# Flex-touch.net
KiCad netlist of a schematic drawn in EasyEDA Pro
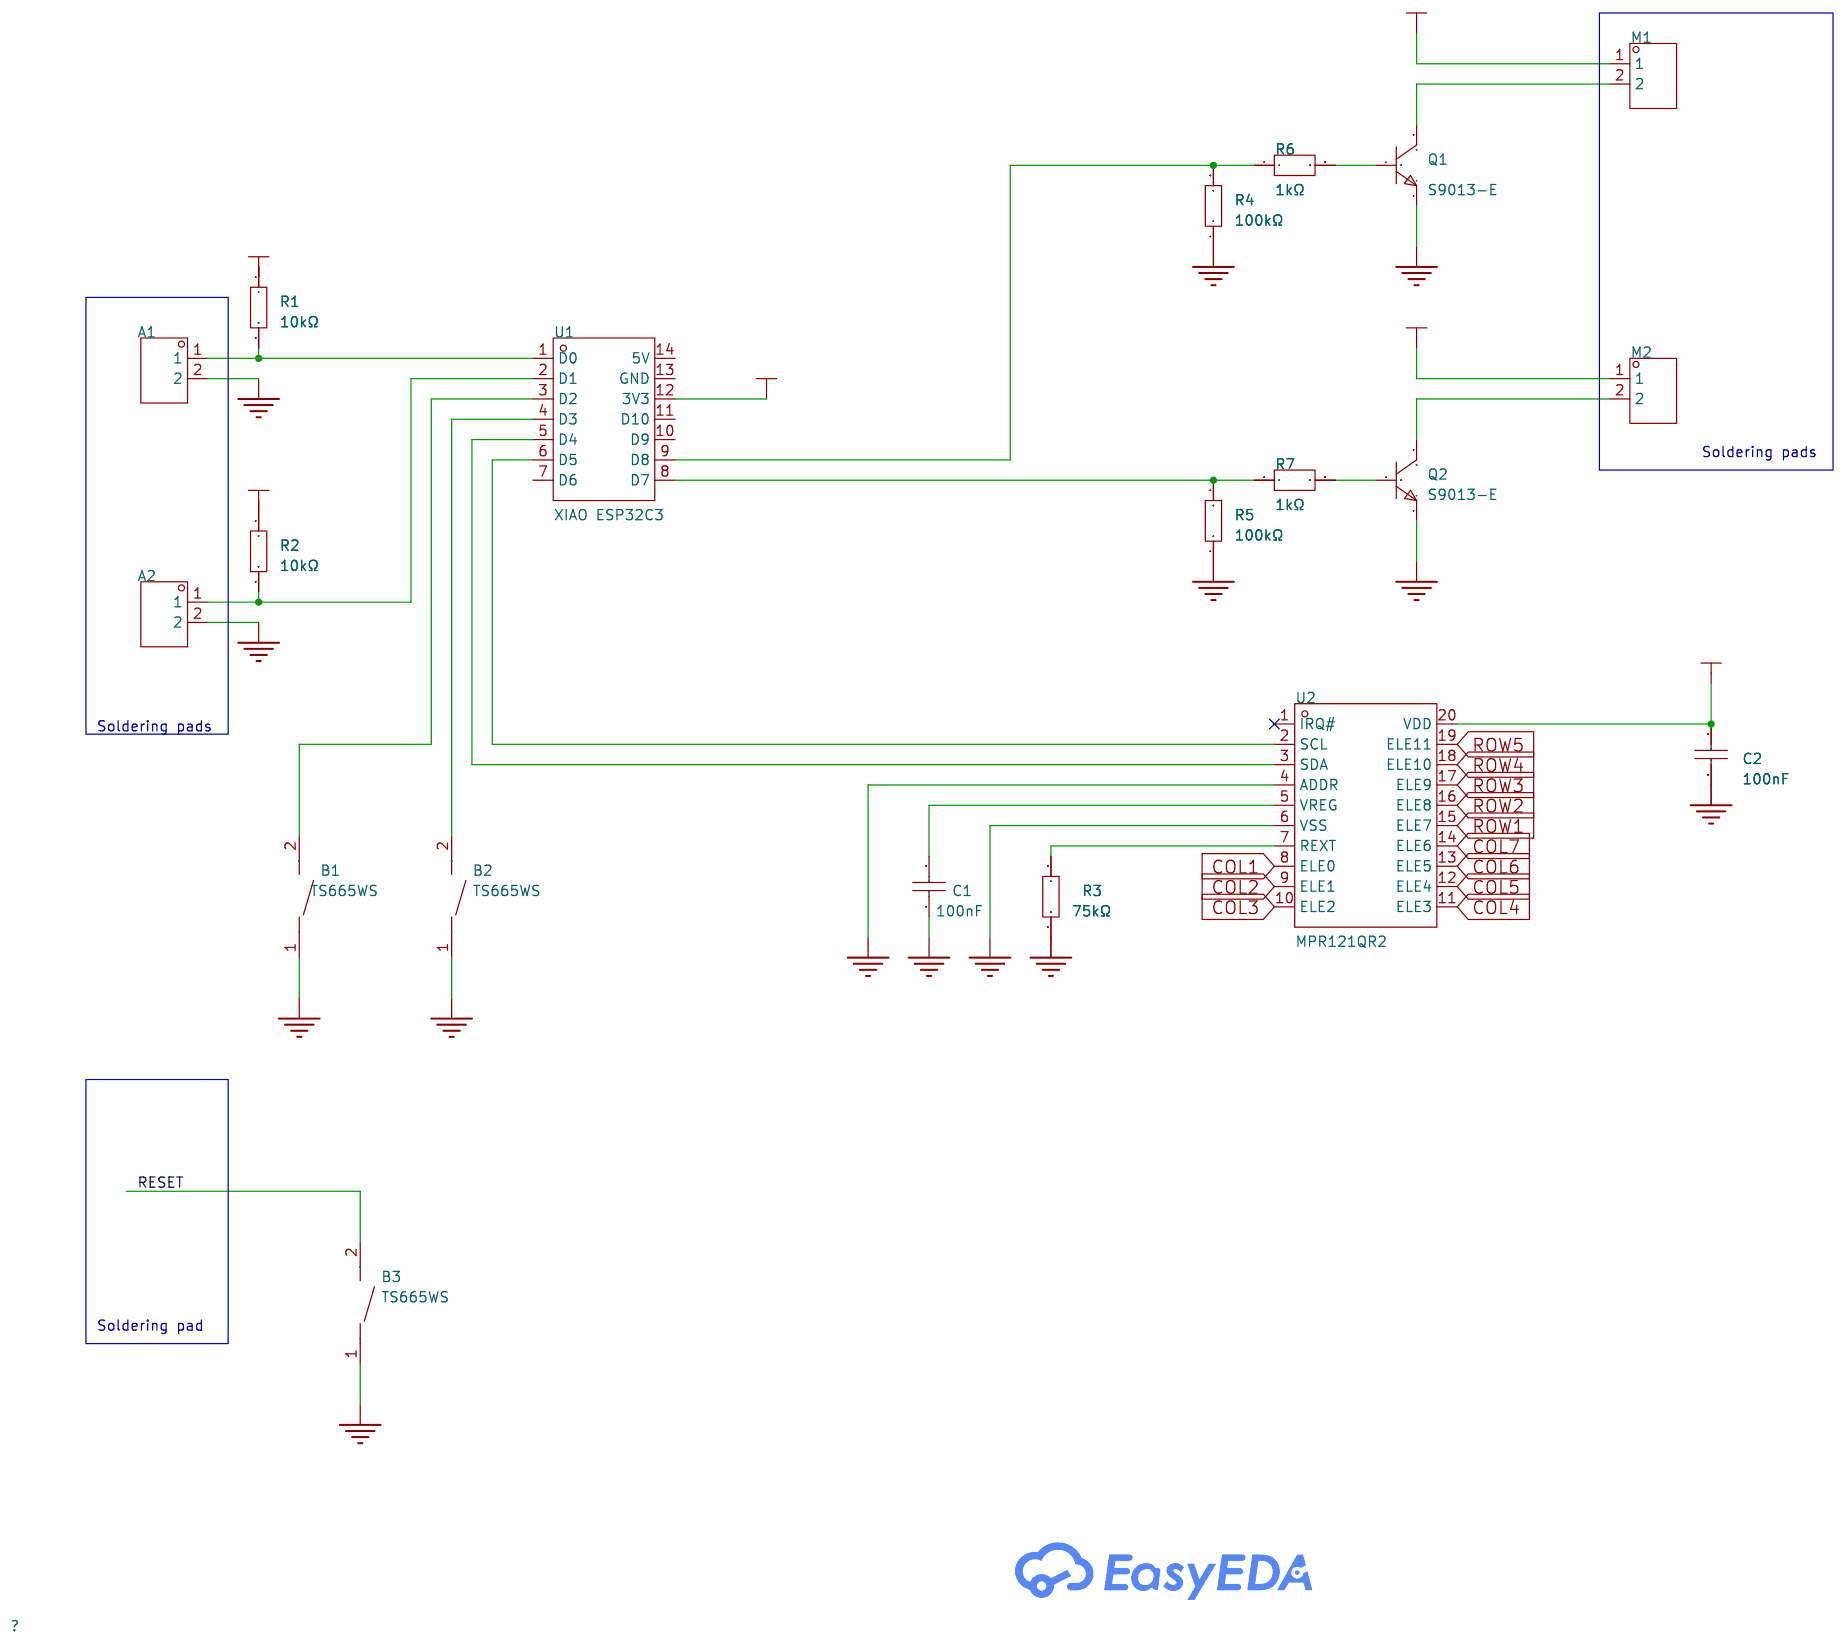
[diagram p0: schematic sheet]

(export (version "E")
  (design (tool "Eeschema 10.0.6"))
  (components
    (comp (ref "A1")
      (value "B-2200S02P-A120")
      (footprint "easyedapro:HDR-TH_2P-P2.54-V-F")
      (description "插孔结构:1x2P;间距:2.54mm;行距:-;安装类型:直插;排数:单排;总孔位数:2P;塑高:-;触头材质:黄铜;触头镀层:-;")
      (fields (field (name "Manufacturer") "Ckmtw(灿科盟)"))
      (libsource (lib "easyedapro") (part "220S-1*2P H=8.5MM Ytype Gold-plated"))
    )
    (comp (ref "A2")
      (value "B-2200S02P-A120")
      (footprint "easyedapro:HDR-TH_2P-P2.54-V-F")
      (description "插孔结构:1x2P;间距:2.54mm;行距:-;安装类型:直插;排数:单排;总孔位数:2P;塑高:-;触头材质:黄铜;触头镀层:-;")
      (fields (field (name "Manufacturer") "Ckmtw(灿科盟)"))
      (libsource (lib "easyedapro") (part "220S-1*2P H=8.5MM Ytype Gold-plated"))
    )
    (comp (ref "B1")
      (value "TS665WS")
      (footprint "easyedapro:SW-SMD_L6.0-W6.0-LS6.6")
      (fields (field (name "Manufacturer") "SHOU HAN(首韩)"))
      (libsource (lib "easyedapro") (part "TS665WS"))
    )
    (comp (ref "B2")
      (value "TS665WS")
      (footprint "easyedapro:SW-SMD_L6.0-W6.0-LS6.6")
      (fields (field (name "Manufacturer") "SHOU HAN(首韩)"))
      (libsource (lib "easyedapro") (part "TS665WS"))
    )
    (comp (ref "B3")
      (value "TS665WS")
      (footprint "easyedapro:SW-SMD_L6.0-W6.0-LS6.6")
      (fields (field (name "Manufacturer") "SHOU HAN(首韩)"))
      (libsource (lib "easyedapro") (part "TS665WS"))
    )
    (comp (ref "C1")
      (value "100nF")
      (footprint "easyedapro:C0603")
      (description "Capacitance:100nF Tolerance:±10% Tolerance:±10% Voltage Rating:50V Temperature Coefficient:X7R")
      (fields (field (name "Manufacturer Part") "0603B104K500NT") (field (name "Manufacturer") "FH(风华)"))
      (libsource (lib "easyedapro") (part "0603B104K500NT"))
    )
    (comp (ref "C2")
      (value "100nF")
      (footprint "easyedapro:C0603")
      (description "Capacitance:100nF Tolerance:±10% Tolerance:±10% Voltage Rating:50V Temperature Coefficient:X7R")
      (fields (field (name "Manufacturer Part") "0603B104K500NT") (field (name "Manufacturer") "FH(风华)"))
      (libsource (lib "easyedapro") (part "0603B104K500NT"))
    )
    (comp (ref "M1")
      (value "B-2200S02P-A120")
      (footprint "easyedapro:HDR-TH_2P-P2.54-V-F")
      (description "插孔结构:1x2P;间距:2.54mm;行距:-;安装类型:直插;排数:单排;总孔位数:2P;塑高:-;触头材质:黄铜;触头镀层:-;")
      (fields (field (name "Manufacturer") "Ckmtw(灿科盟)"))
      (libsource (lib "easyedapro") (part "220S-1*2P H=8.5MM Ytype Gold-plated"))
    )
    (comp (ref "M2")
      (value "B-2200S02P-A120")
      (footprint "easyedapro:HDR-TH_2P-P2.54-V-F")
      (description "插孔结构:1x2P;间距:2.54mm;行距:-;安装类型:直插;排数:单排;总孔位数:2P;塑高:-;触头材质:黄铜;触头镀层:-;")
      (fields (field (name "Manufacturer") "Ckmtw(灿科盟)"))
      (libsource (lib "easyedapro") (part "220S-1*2P H=8.5MM Ytype Gold-plated"))
    )
    (comp (ref "Q1")
      (value "S9013-E")
      (footprint "easyedapro:SOT-23-3_L2.9-W1.3-P1.90-LS2.4-BR")
      (description "晶体管类型:NPN;集电极电流(Ic):500mA;集射极击穿电压(Vceo):25V;耗散功率(Pd):300mW;直流电流增益(hFE):120@50mA,1V;")
      (fields (field (name "Manufacturer") "MDD(辰达半导体)"))
      (libsource (lib "easyedapro") (part "S9013-E"))
    )
    (comp (ref "Q2")
      (value "S9013-E")
      (footprint "easyedapro:SOT-23-3_L2.9-W1.3-P1.90-LS2.4-BR")
      (description "晶体管类型:NPN;集电极电流(Ic):500mA;集射极击穿电压(Vceo):25V;耗散功率(Pd):300mW;直流电流增益(hFE):120@50mA,1V;")
      (fields (field (name "Manufacturer") "MDD(辰达半导体)"))
      (libsource (lib "easyedapro") (part "S9013-E"))
    )
    (comp (ref "R1")
      (value "10kΩ")
      (footprint "easyedapro:R0603")
      (fields (field (name "Manufacturer Part") "RC0603FR-0710KL") (field (name "Manufacturer") "YAGEO(国巨)"))
      (libsource (lib "easyedapro") (part "RC0603FR-0710KL"))
    )
    (comp (ref "R2")
      (value "10kΩ")
      (footprint "easyedapro:R0603")
      (fields (field (name "Manufacturer Part") "RC0603FR-0710KL") (field (name "Manufacturer") "YAGEO(国巨)"))
      (libsource (lib "easyedapro") (part "RC0603FR-0710KL"))
    )
    (comp (ref "R3")
      (value "75kΩ")
      (footprint "easyedapro:R0603")
      (fields (field (name "Manufacturer Part") "RTT03753JTP") (field (name "Manufacturer") "RALEC(旺诠)"))
      (libsource (lib "easyedapro") (part "RTT03753JTP"))
    )
    (comp (ref "R4")
      (value "100kΩ")
      (footprint "easyedapro:R0603")
      (description "电阻类型:厚膜电阻;阻值:100kΩ;精度:±1%;功率:100mW;最大工作电压:75V;温度系数:±100ppm/°C;")
      (fields
        (field (name "Manufacturer Part") "0603WAF1003T5E")
        (field (name "Manufacturer") "UNI-ROYAL(厚声)")
      )
      (libsource (lib "easyedapro") (part "0603WAF1003T5E"))
    )
    (comp (ref "R5")
      (value "100kΩ")
      (footprint "easyedapro:R0603")
      (description "电阻类型:厚膜电阻;阻值:100kΩ;精度:±1%;功率:100mW;最大工作电压:75V;温度系数:±100ppm/°C;")
      (fields
        (field (name "Manufacturer Part") "0603WAF1003T5E")
        (field (name "Manufacturer") "UNI-ROYAL(厚声)")
      )
      (libsource (lib "easyedapro") (part "0603WAF1003T5E"))
    )
    (comp (ref "R6")
      (value "1kΩ")
      (footprint "easyedapro:R0603")
      (description "电阻类型:厚膜电阻;阻值:1kΩ;精度:±5%;功率:100mW;最大工作电压:75V;")
      (fields (field (name "Manufacturer Part") "SCR0603J1K") (field (name "Manufacturer") "VO(翔胜)"))
      (libsource (lib "easyedapro") (part "SCR0603J1K"))
    )
    (comp (ref "R7")
      (value "1kΩ")
      (footprint "easyedapro:R0603")
      (description "电阻类型:厚膜电阻;阻值:1kΩ;精度:±5%;功率:100mW;最大工作电压:75V;")
      (fields (field (name "Manufacturer Part") "SCR0603J1K") (field (name "Manufacturer") "VO(翔胜)"))
      (libsource (lib "easyedapro") (part "SCR0603J1K"))
    )
    (comp (ref "U1")
      (value "XIAO ESP32C3")
      (footprint "easyedapro:COMM-SMD_KQ-2801_V106")
      (libsource (lib "easyedapro") (part "XIAO ESP32C3"))
    )
    (comp (ref "U2")
      (value "MPR121QR2")
      (footprint "easyedapro:QFN-20_L3.0-W3.0-P0.40-BL")
      (fields (field (name "Manufacturer") "NXP(恩智浦)"))
      (libsource (lib "easyedapro") (part "MPR121QR2"))
    )
  )
  (nets
    (net (code "1") (name "/RESET") (class "Default")
      (node (ref "B3") (pin "2") (pinfunction "B_2") (pintype "unspecified"))
    )
    (net (code "2") (name "3V3") (class "Default")
      (node (ref "C2") (pin "2") (pinfunction "2_2") (pintype "input"))
      (node (ref "M1") (pin "1") (pinfunction "1_1") (pintype "unspecified"))
      (node (ref "M2") (pin "1") (pinfunction "1_1") (pintype "unspecified"))
      (node (ref "R1") (pin "1") (pinfunction "1_1") (pintype "input"))
      (node (ref "R2") (pin "1") (pinfunction "1_1") (pintype "input"))
      (node (ref "U1") (pin "12") (pinfunction "3V3_12") (pintype "unspecified"))
      (node (ref "U2") (pin "20") (pinfunction "VDD_20") (pintype "unspecified"))
    )
    (net (code "3") (name "COL1") (class "Default")
      (node (ref "U2") (pin "8") (pinfunction "ELE0_8") (pintype "unspecified"))
    )
    (net (code "4") (name "COL2") (class "Default")
      (node (ref "U2") (pin "9") (pinfunction "ELE1_9") (pintype "unspecified"))
    )
    (net (code "5") (name "COL3") (class "Default")
      (node (ref "U2") (pin "10") (pinfunction "ELE2_10") (pintype "unspecified"))
    )
    (net (code "6") (name "COL4") (class "Default")
      (node (ref "U2") (pin "11") (pinfunction "ELE3_11") (pintype "unspecified"))
    )
    (net (code "7") (name "COL5") (class "Default")
      (node (ref "U2") (pin "12") (pinfunction "ELE4_12") (pintype "unspecified"))
    )
    (net (code "8") (name "COL6") (class "Default")
      (node (ref "U2") (pin "13") (pinfunction "ELE5_13") (pintype "unspecified"))
    )
    (net (code "9") (name "COL7") (class "Default")
      (node (ref "U2") (pin "14") (pinfunction "ELE6_14") (pintype "unspecified"))
    )
    (net (code "10") (name "GND") (class "Default")
      (node (ref "A1") (pin "2") (pinfunction "2_2") (pintype "unspecified"))
      (node (ref "A2") (pin "2") (pinfunction "2_2") (pintype "unspecified"))
      (node (ref "B1") (pin "1") (pinfunction "A_1") (pintype "unspecified"))
      (node (ref "B2") (pin "1") (pinfunction "A_1") (pintype "unspecified"))
      (node (ref "B3") (pin "1") (pinfunction "A_1") (pintype "unspecified"))
      (node (ref "C1") (pin "1") (pinfunction "1_1") (pintype "input"))
      (node (ref "C2") (pin "1") (pinfunction "1_1") (pintype "input"))
      (node (ref "Q1") (pin "2") (pinfunction "E_2") (pintype "input"))
      (node (ref "Q2") (pin "2") (pinfunction "E_2") (pintype "input"))
      (node (ref "R3") (pin "1") (pinfunction "1_1") (pintype "input"))
      (node (ref "R4") (pin "1") (pinfunction "1_1") (pintype "input"))
      (node (ref "R5") (pin "1") (pinfunction "1_1") (pintype "input"))
      (node (ref "U2") (pin "4") (pinfunction "ADDR_4") (pintype "unspecified"))
      (node (ref "U2") (pin "6") (pinfunction "VSS_6") (pintype "unspecified"))
    )
    (net (code "11") (name "Net-(B1-B)") (class "Default")
      (node (ref "B1") (pin "2") (pinfunction "B_2") (pintype "unspecified"))
      (node (ref "U1") (pin "3") (pinfunction "D2_3") (pintype "unspecified"))
    )
    (net (code "12") (name "Net-(B2-B)") (class "Default")
      (node (ref "B2") (pin "2") (pinfunction "B_2") (pintype "unspecified"))
      (node (ref "U1") (pin "4") (pinfunction "D3_4") (pintype "unspecified"))
    )
    (net (code "13") (name "Net-(Q1-B)") (class "Default")
      (node (ref "Q1") (pin "1") (pinfunction "B_1") (pintype "input"))
      (node (ref "R6") (pin "2") (pinfunction "2_2") (pintype "unspecified"))
    )
    (net (code "14") (name "Net-(Q1-C)") (class "Default")
      (node (ref "M1") (pin "2") (pinfunction "2_2") (pintype "unspecified"))
      (node (ref "Q1") (pin "3") (pinfunction "C_3") (pintype "input"))
    )
    (net (code "15") (name "Net-(Q2-B)") (class "Default")
      (node (ref "Q2") (pin "1") (pinfunction "B_1") (pintype "input"))
      (node (ref "R7") (pin "2") (pinfunction "2_2") (pintype "unspecified"))
    )
    (net (code "16") (name "Net-(Q2-C)") (class "Default")
      (node (ref "M2") (pin "2") (pinfunction "2_2") (pintype "unspecified"))
      (node (ref "Q2") (pin "3") (pinfunction "C_3") (pintype "input"))
    )
    (net (code "17") (name "Net-(U1-D0)") (class "Default")
      (node (ref "A1") (pin "1") (pinfunction "1_1") (pintype "unspecified"))
      (node (ref "R1") (pin "2") (pinfunction "2_2") (pintype "input"))
      (node (ref "U1") (pin "1") (pinfunction "D0_1") (pintype "unspecified"))
    )
    (net (code "18") (name "Net-(U1-D1)") (class "Default")
      (node (ref "A2") (pin "1") (pinfunction "1_1") (pintype "unspecified"))
      (node (ref "R2") (pin "2") (pinfunction "2_2") (pintype "input"))
      (node (ref "U1") (pin "2") (pinfunction "D1_2") (pintype "unspecified"))
    )
    (net (code "19") (name "Net-(U1-D4)") (class "Default")
      (node (ref "U1") (pin "5") (pinfunction "D4_5") (pintype "unspecified"))
      (node (ref "U2") (pin "3") (pinfunction "SDA_3") (pintype "unspecified"))
    )
    (net (code "20") (name "Net-(U1-D5)") (class "Default")
      (node (ref "U1") (pin "6") (pinfunction "D5_6") (pintype "unspecified"))
      (node (ref "U2") (pin "2") (pinfunction "SCL_2") (pintype "unspecified"))
    )
    (net (code "21") (name "Net-(U1-D7)") (class "Default")
      (node (ref "R5") (pin "2") (pinfunction "2_2") (pintype "input"))
      (node (ref "R7") (pin "1") (pinfunction "1_1") (pintype "unspecified"))
      (node (ref "U1") (pin "8") (pinfunction "D7_8") (pintype "unspecified"))
    )
    (net (code "22") (name "Net-(U1-D8)") (class "Default")
      (node (ref "R4") (pin "2") (pinfunction "2_2") (pintype "input"))
      (node (ref "R6") (pin "1") (pinfunction "1_1") (pintype "unspecified"))
      (node (ref "U1") (pin "9") (pinfunction "D8_9") (pintype "unspecified"))
    )
    (net (code "23") (name "Net-(U2-REXT)") (class "Default")
      (node (ref "R3") (pin "2") (pinfunction "2_2") (pintype "input"))
      (node (ref "U2") (pin "7") (pinfunction "REXT_7") (pintype "unspecified"))
    )
    (net (code "24") (name "Net-(U2-VREG)") (class "Default")
      (node (ref "C1") (pin "2") (pinfunction "2_2") (pintype "input"))
      (node (ref "U2") (pin "5") (pinfunction "VREG_5") (pintype "unspecified"))
    )
    (net (code "25") (name "ROW1") (class "Default")
      (node (ref "U2") (pin "15") (pinfunction "ELE7_15") (pintype "unspecified"))
    )
    (net (code "26") (name "ROW2") (class "Default")
      (node (ref "U2") (pin "16") (pinfunction "ELE8_16") (pintype "unspecified"))
    )
    (net (code "27") (name "ROW3") (class "Default")
      (node (ref "U2") (pin "17") (pinfunction "ELE9_17") (pintype "unspecified"))
    )
    (net (code "28") (name "ROW4") (class "Default")
      (node (ref "U2") (pin "18") (pinfunction "ELE10_18") (pintype "unspecified"))
    )
    (net (code "29") (name "ROW5") (class "Default")
      (node (ref "U2") (pin "19") (pinfunction "ELE11_19") (pintype "unspecified"))
    )
    (net (code "30") (name "unconnected-(U1-5V-Pad14)") (class "Default")
      (node (ref "U1") (pin "14") (pinfunction "5V_14") (pintype "unspecified"))
    )
    (net (code "31") (name "unconnected-(U1-D6-Pad7)") (class "Default")
      (node (ref "U1") (pin "7") (pinfunction "D6_7") (pintype "unspecified"))
    )
    (net (code "32") (name "unconnected-(U1-D9-Pad10)") (class "Default")
      (node (ref "U1") (pin "10") (pinfunction "D9_10") (pintype "unspecified"))
    )
    (net (code "33") (name "unconnected-(U1-D10-Pad11)") (class "Default")
      (node (ref "U1") (pin "11") (pinfunction "D10_11") (pintype "unspecified"))
    )
    (net (code "34") (name "unconnected-(U1-GND-Pad13)") (class "Default")
      (node (ref "U1") (pin "13") (pinfunction "GND_13") (pintype "unspecified"))
    )
    (net (code "35") (name "unconnected-(U2-IRQ#-Pad1)") (class "Default")
      (node (ref "U2") (pin "1") (pinfunction "IRQ#_1") (pintype "unspecified+no_connect"))
    )
  )
)
